# rapidshark_mark_3_5_fuckit.net
KiCad netlist of a schematic drawn in EAGLE
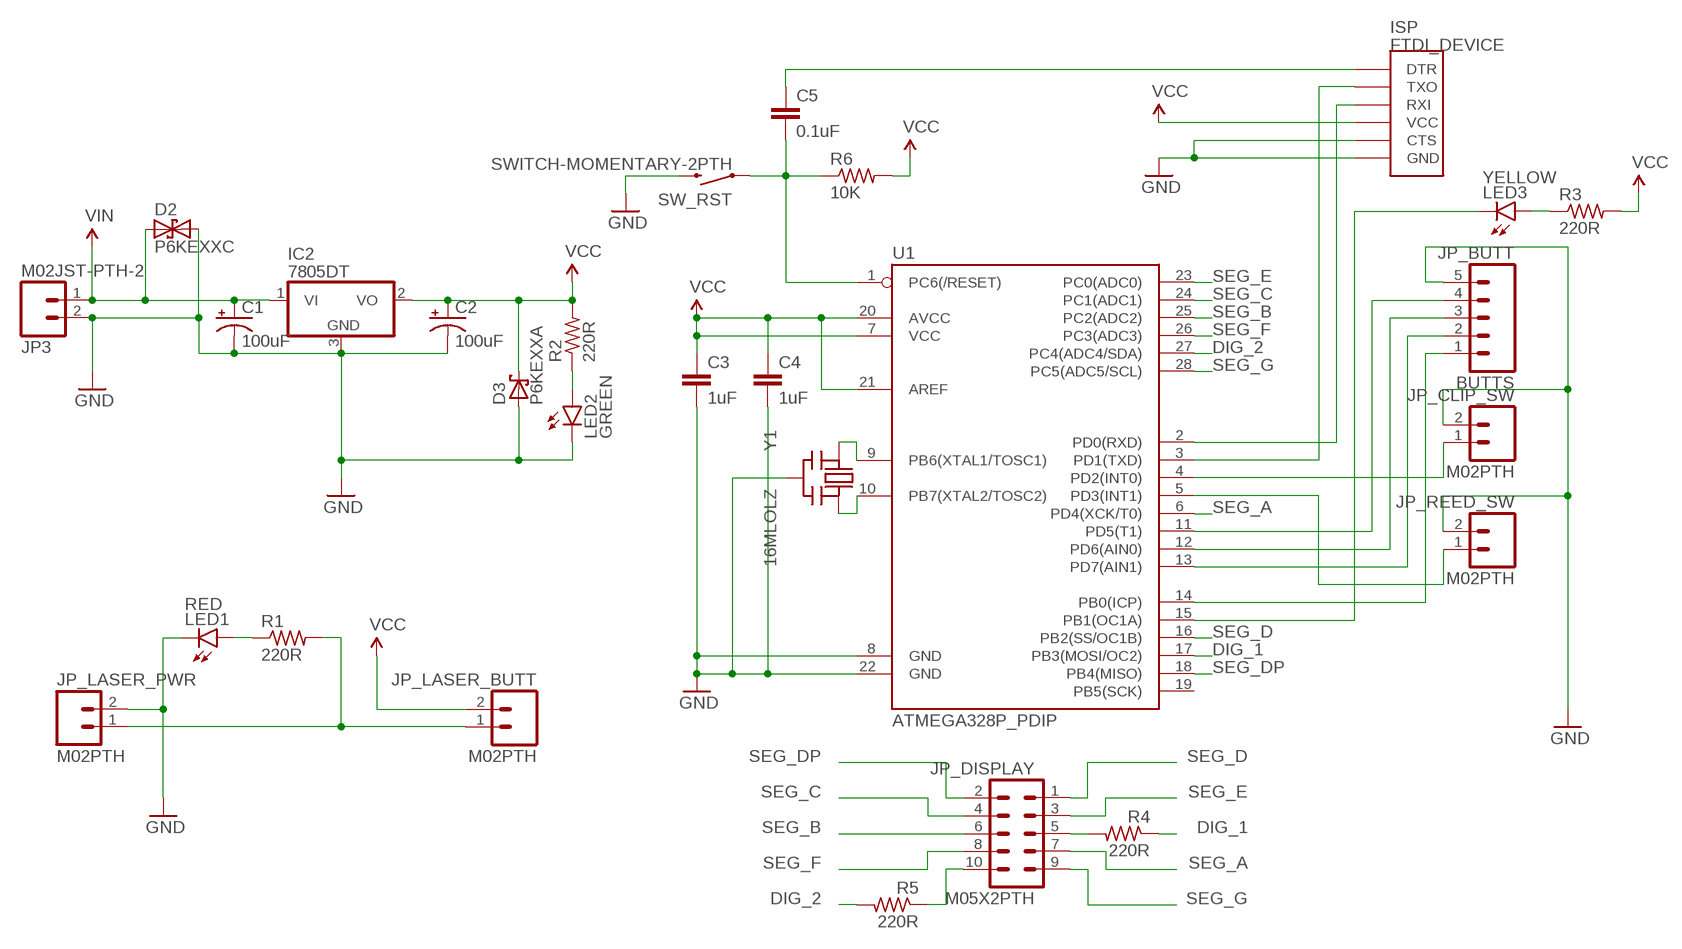
[diagram p0: schematic, sheet 1]

(export (version "E")
  (design (tool "Eeschema 10.0.6"))
  (components
    (comp (ref "C1")
      (value "100uF")
      (footprint "eagle-import:TT2D7L")
      (libsource (lib "eagle-import") (part "CPOL-USTT2D7L"))
    )
    (comp (ref "C2")
      (value "100uF")
      (footprint "eagle-import:TT2D7L")
      (libsource (lib "eagle-import") (part "CPOL-USTT2D7L"))
    )
    (comp (ref "C3")
      (value "1uF")
      (footprint "eagle-import:C025-025X050")
      (libsource (lib "eagle-import") (part "C-EU025-025X050"))
    )
    (comp (ref "C4")
      (value "1uF")
      (footprint "eagle-import:C050-024X044")
      (libsource (lib "eagle-import") (part "C-EU050-024X044"))
    )
    (comp (ref "C5")
      (value "0.1uF")
      (footprint "eagle-import:C025-024X044")
      (libsource (lib "eagle-import") (part "C-EU025-024X044"))
    )
    (comp (ref "D2")
      (value "P6KEXXC")
      (footprint "eagle-import:CB417-15")
      (libsource (lib "eagle-import") (part "P6KEXXC"))
    )
    (comp (ref "D3")
      (value "P6KEXXA")
      (footprint "eagle-import:C1702-15")
      (libsource (lib "eagle-import") (part "P6KEXXA"))
    )
    (comp (ref "IC2")
      (value "7805DT")
      (footprint "eagle-import:TO252")
      (libsource (lib "eagle-import") (part "78DT05"))
    )
    (comp (ref "ISP")
      (value "FTDI_DEVICE")
      (footprint "eagle-import:FTDI_DEVICE_SIDE")
      (libsource (lib "eagle-import") (part "FTDI_DEVICE"))
    )
    (comp (ref "JP3")
      (value "M02JST-PTH-2")
      (footprint "eagle-import:JST-2-PTH")
      (libsource (lib "eagle-import") (part "M02JST-PTH-2"))
    )
    (comp (ref "JP_BUTT")
      (value "BUTTS")
      (footprint "eagle-import:1X05")
      (libsource (lib "eagle-import") (part "M05PTH"))
    )
    (comp (ref "JP_CLIP_SW")
      (value "M02PTH")
      (footprint "eagle-import:1X02")
      (libsource (lib "eagle-import") (part "M02PTH"))
    )
    (comp (ref "JP_DISPLAY")
      (value "M05X2PTH")
      (footprint "eagle-import:AVR_ICSP")
      (libsource (lib "eagle-import") (part "M05X2PTH"))
    )
    (comp (ref "JP_LASER_BUTT")
      (value "M02PTH")
      (footprint "eagle-import:1X02")
      (libsource (lib "eagle-import") (part "M02PTH"))
    )
    (comp (ref "JP_LASER_PWR")
      (value "M02PTH")
      (footprint "eagle-import:1X02")
      (libsource (lib "eagle-import") (part "M02PTH"))
    )
    (comp (ref "JP_REED_SW")
      (value "M02PTH")
      (footprint "eagle-import:1X02")
      (libsource (lib "eagle-import") (part "M02PTH"))
    )
    (comp (ref "LED1")
      (value "RED")
      (footprint "eagle-import:LED3MM")
      (libsource (lib "eagle-import") (part "LED3MM"))
    )
    (comp (ref "LED2")
      (value "GREEN")
      (footprint "eagle-import:LED3MM")
      (libsource (lib "eagle-import") (part "LED3MM"))
    )
    (comp (ref "LED3")
      (value "YELLOW")
      (footprint "eagle-import:LED3MM")
      (libsource (lib "eagle-import") (part "LED3MM"))
    )
    (comp (ref "R1")
      (value "220R")
      (footprint "eagle-import:0204_5")
      (libsource (lib "eagle-import") (part "R-US_0204/5"))
    )
    (comp (ref "R2")
      (value "220R")
      (footprint "eagle-import:0204_5")
      (libsource (lib "eagle-import") (part "R-US_0204/5"))
    )
    (comp (ref "R3")
      (value "220R")
      (footprint "eagle-import:0204_5")
      (libsource (lib "eagle-import") (part "R-US_0204/5"))
    )
    (comp (ref "R4")
      (value "220R")
      (footprint "eagle-import:0204_5")
      (libsource (lib "eagle-import") (part "R-US_0204/5"))
    )
    (comp (ref "R5")
      (value "220R")
      (footprint "eagle-import:0204_5")
      (libsource (lib "eagle-import") (part "R-US_0204/5"))
    )
    (comp (ref "R6")
      (value "10K")
      (footprint "eagle-import:0204_5")
      (libsource (lib "eagle-import") (part "R-US_0204/5"))
    )
    (comp (ref "SW_RST")
      (value "SWITCH-MOMENTARY-2PTH")
      (footprint "eagle-import:TACTILE-PTH")
      (libsource (lib "eagle-import") (part "SWITCH-MOMENTARY-2PTH"))
    )
    (comp (ref "U1")
      (value "ATMEGA328P_PDIP")
      (footprint "eagle-import:DIL28-3")
      (libsource (lib "eagle-import") (part "ATMEGA328P_PDIP"))
    )
    (comp (ref "Y1")
      (value "16MLOLZ")
      (footprint "eagle-import:CERM_OSC")
      (libsource (lib "eagle-import") (part "CERMOSCILL-THM"))
    )
  )
  (nets
    (net (code "1") (name "/DIG_1") (class "Default")
      (node (ref "R4") (pin "1") (pinfunction "1_1") (pintype "passive"))
      (node (ref "U1") (pin "17") (pinfunction "PB3(MOSI/OC2)_17") (pintype "bidirectional"))
    )
    (net (code "2") (name "/DIG_2") (class "Default")
      (node (ref "R5") (pin "2") (pinfunction "2_2") (pintype "passive"))
      (node (ref "U1") (pin "27") (pinfunction "PC4(ADC4/SDA)_27") (pintype "bidirectional"))
    )
    (net (code "3") (name "/SEG_A") (class "Default")
      (node (ref "JP_DISPLAY") (pin "7") (pinfunction "7_7") (pintype "passive"))
      (node (ref "U1") (pin "6") (pinfunction "PD4(XCK/T0)_6") (pintype "bidirectional"))
    )
    (net (code "4") (name "/SEG_B") (class "Default")
      (node (ref "JP_DISPLAY") (pin "6") (pinfunction "6_6") (pintype "passive"))
      (node (ref "U1") (pin "25") (pinfunction "PC2(ADC2)_25") (pintype "bidirectional"))
    )
    (net (code "5") (name "/SEG_C") (class "Default")
      (node (ref "JP_DISPLAY") (pin "4") (pinfunction "4_4") (pintype "passive"))
      (node (ref "U1") (pin "24") (pinfunction "PC1(ADC1)_24") (pintype "bidirectional"))
    )
    (net (code "6") (name "/SEG_D") (class "Default")
      (node (ref "JP_DISPLAY") (pin "1") (pinfunction "1_1") (pintype "passive"))
      (node (ref "U1") (pin "16") (pinfunction "PB2(SS/OC1B)_16") (pintype "bidirectional"))
    )
    (net (code "7") (name "/SEG_DP") (class "Default")
      (node (ref "JP_DISPLAY") (pin "2") (pinfunction "2_2") (pintype "passive"))
      (node (ref "U1") (pin "18") (pinfunction "PB4(MISO)_18") (pintype "bidirectional"))
    )
    (net (code "8") (name "/SEG_E") (class "Default")
      (node (ref "JP_DISPLAY") (pin "3") (pinfunction "3_3") (pintype "passive"))
      (node (ref "U1") (pin "23") (pinfunction "PC0(ADC0)_23") (pintype "bidirectional"))
    )
    (net (code "9") (name "/SEG_F") (class "Default")
      (node (ref "JP_DISPLAY") (pin "8") (pinfunction "8_8") (pintype "passive"))
      (node (ref "U1") (pin "26") (pinfunction "PC3(ADC3)_26") (pintype "bidirectional"))
    )
    (net (code "10") (name "/SEG_G") (class "Default")
      (node (ref "JP_DISPLAY") (pin "9") (pinfunction "9_9") (pintype "passive"))
      (node (ref "U1") (pin "28") (pinfunction "PC5(ADC5/SCL)_28") (pintype "bidirectional"))
    )
    (net (code "11") (name "GND") (class "Default")
      (node (ref "C1") (pin "-") (pinfunction "-_-") (pintype "passive"))
      (node (ref "C2") (pin "-") (pinfunction "-_-") (pintype "passive"))
      (node (ref "C3") (pin "2") (pinfunction "2_2") (pintype "passive"))
      (node (ref "C4") (pin "2") (pinfunction "2_2") (pintype "passive"))
      (node (ref "D2") (pin "C") (pinfunction "2_C") (pintype "passive"))
      (node (ref "D3") (pin "A") (pinfunction "A_A") (pintype "passive"))
      (node (ref "IC2") (pin "3") (pinfunction "GND_3") (pintype "passive"))
      (node (ref "ISP") (pin "P$5") (pinfunction "CTS_P$5") (pintype "bidirectional"))
      (node (ref "ISP") (pin "P$6") (pinfunction "GND_P$6") (pintype "bidirectional"))
      (node (ref "JP3") (pin "2") (pinfunction "2_2") (pintype "passive"))
      (node (ref "JP_BUTT") (pin "5") (pinfunction "5_5") (pintype "passive"))
      (node (ref "JP_CLIP_SW") (pin "2") (pinfunction "2_2") (pintype "passive"))
      (node (ref "JP_LASER_PWR") (pin "2") (pinfunction "2_2") (pintype "passive"))
      (node (ref "JP_REED_SW") (pin "2") (pinfunction "2_2") (pintype "passive"))
      (node (ref "LED1") (pin "K") (pinfunction "C_K") (pintype "passive"))
      (node (ref "LED2") (pin "K") (pinfunction "C_K") (pintype "passive"))
      (node (ref "SW_RST") (pin "3") (pinfunction "2_3") (pintype "passive"))
      (node (ref "U1") (pin "22") (pinfunction "GND_22") (pintype "bidirectional"))
      (node (ref "U1") (pin "8") (pinfunction "GND_8") (pintype "bidirectional"))
      (node (ref "Y1") (pin "P$2") (pinfunction "GND_P$2") (pintype "bidirectional"))
    )
    (net (code "12") (name "Net-(ISP-DTR)") (class "Default")
      (node (ref "C5") (pin "1") (pinfunction "1_1") (pintype "passive"))
      (node (ref "ISP") (pin "P$1") (pinfunction "DTR_P$1") (pintype "bidirectional"))
    )
    (net (code "13") (name "Net-(ISP-RXI)") (class "Default")
      (node (ref "ISP") (pin "P$3") (pinfunction "RXI_P$3") (pintype "bidirectional"))
      (node (ref "U1") (pin "2") (pinfunction "PD0(RXD)_2") (pintype "bidirectional"))
    )
    (net (code "14") (name "Net-(ISP-TXO)") (class "Default")
      (node (ref "ISP") (pin "P$2") (pinfunction "TXO_P$2") (pintype "bidirectional"))
      (node (ref "U1") (pin "3") (pinfunction "PD1(TXD)_3") (pintype "bidirectional"))
    )
    (net (code "15") (name "Net-(JP_DISPLAY-Pad5)") (class "Default")
      (node (ref "JP_DISPLAY") (pin "5") (pinfunction "5_5") (pintype "passive"))
      (node (ref "R4") (pin "2") (pinfunction "2_2") (pintype "passive"))
    )
    (net (code "16") (name "Net-(JP_DISPLAY-Pad10)") (class "Default")
      (node (ref "JP_DISPLAY") (pin "10") (pinfunction "10_10") (pintype "passive"))
      (node (ref "R5") (pin "1") (pinfunction "1_1") (pintype "passive"))
    )
    (net (code "17") (name "Net-(JP_LASER_BUTT-Pad1)") (class "Default")
      (node (ref "JP_LASER_BUTT") (pin "1") (pinfunction "1_1") (pintype "passive"))
      (node (ref "JP_LASER_PWR") (pin "1") (pinfunction "1_1") (pintype "passive"))
      (node (ref "R1") (pin "2") (pinfunction "2_2") (pintype "passive"))
    )
    (net (code "18") (name "Net-(LED1-PadA)") (class "Default")
      (node (ref "LED1") (pin "A") (pinfunction "A_A") (pintype "passive"))
      (node (ref "R1") (pin "1") (pinfunction "1_1") (pintype "passive"))
    )
    (net (code "19") (name "Net-(LED2-PadA)") (class "Default")
      (node (ref "LED2") (pin "A") (pinfunction "A_A") (pintype "passive"))
      (node (ref "R2") (pin "1") (pinfunction "1_1") (pintype "passive"))
    )
    (net (code "20") (name "Net-(LED3-C)") (class "Default")
      (node (ref "LED3") (pin "K") (pinfunction "C_K") (pintype "passive"))
      (node (ref "U1") (pin "15") (pinfunction "PB1(OC1A)_15") (pintype "bidirectional"))
    )
    (net (code "21") (name "Net-(LED3-PadA)") (class "Default")
      (node (ref "LED3") (pin "A") (pinfunction "A_A") (pintype "passive"))
      (node (ref "R3") (pin "1") (pinfunction "1_1") (pintype "passive"))
    )
    (net (code "22") (name "Net-(U1-PB0(ICP))") (class "Default")
      (node (ref "JP_BUTT") (pin "1") (pinfunction "1_1") (pintype "passive"))
      (node (ref "U1") (pin "14") (pinfunction "PB0(ICP)_14") (pintype "bidirectional"))
    )
    (net (code "23") (name "Net-(U1-PB6(XTAL1{slash}TOSC1))") (class "Default")
      (node (ref "U1") (pin "9") (pinfunction "PB6(XTAL1/TOSC1)_9") (pintype "bidirectional"))
      (node (ref "Y1") (pin "P$1") (pinfunction "IN_P$1") (pintype "bidirectional"))
    )
    (net (code "24") (name "Net-(U1-PB7(XTAL2{slash}TOSC2))") (class "Default")
      (node (ref "U1") (pin "10") (pinfunction "PB7(XTAL2/TOSC2)_10") (pintype "bidirectional"))
      (node (ref "Y1") (pin "P$3") (pinfunction "OUT_P$3") (pintype "bidirectional"))
    )
    (net (code "25") (name "Net-(U1-PC6({slash}RESET))") (class "Default")
      (node (ref "C5") (pin "2") (pinfunction "2_2") (pintype "passive"))
      (node (ref "R6") (pin "1") (pinfunction "1_1") (pintype "passive"))
      (node (ref "SW_RST") (pin "1") (pinfunction "1_1") (pintype "passive"))
      (node (ref "U1") (pin "1") (pinfunction "PC6(/RESET)_1") (pintype "bidirectional"))
    )
    (net (code "26") (name "Net-(U1-PD2(INT0))") (class "Default")
      (node (ref "JP_CLIP_SW") (pin "1") (pinfunction "1_1") (pintype "passive"))
      (node (ref "U1") (pin "4") (pinfunction "PD2(INT0)_4") (pintype "bidirectional"))
    )
    (net (code "27") (name "Net-(U1-PD3(INT1))") (class "Default")
      (node (ref "JP_REED_SW") (pin "1") (pinfunction "1_1") (pintype "passive"))
      (node (ref "U1") (pin "5") (pinfunction "PD3(INT1)_5") (pintype "bidirectional"))
    )
    (net (code "28") (name "Net-(U1-PD5(T1))") (class "Default")
      (node (ref "JP_BUTT") (pin "4") (pinfunction "4_4") (pintype "passive"))
      (node (ref "U1") (pin "11") (pinfunction "PD5(T1)_11") (pintype "bidirectional"))
    )
    (net (code "29") (name "Net-(U1-PD6(AIN0))") (class "Default")
      (node (ref "JP_BUTT") (pin "3") (pinfunction "3_3") (pintype "passive"))
      (node (ref "U1") (pin "12") (pinfunction "PD6(AIN0)_12") (pintype "bidirectional"))
    )
    (net (code "30") (name "Net-(U1-PD7(AIN1))") (class "Default")
      (node (ref "JP_BUTT") (pin "2") (pinfunction "2_2") (pintype "passive"))
      (node (ref "U1") (pin "13") (pinfunction "PD7(AIN1)_13") (pintype "bidirectional"))
    )
    (net (code "31") (name "VCC") (class "Default")
      (node (ref "C2") (pin "+") (pinfunction "+_+") (pintype "passive"))
      (node (ref "C3") (pin "1") (pinfunction "1_1") (pintype "passive"))
      (node (ref "C4") (pin "1") (pinfunction "1_1") (pintype "passive"))
      (node (ref "D3") (pin "C") (pinfunction "C_C") (pintype "passive"))
      (node (ref "IC2") (pin "2") (pinfunction "VO_2") (pintype "passive"))
      (node (ref "ISP") (pin "P$4") (pinfunction "VCC_P$4") (pintype "bidirectional"))
      (node (ref "JP_LASER_BUTT") (pin "2") (pinfunction "2_2") (pintype "passive"))
      (node (ref "R2") (pin "2") (pinfunction "2_2") (pintype "passive"))
      (node (ref "R3") (pin "2") (pinfunction "2_2") (pintype "passive"))
      (node (ref "R6") (pin "2") (pinfunction "2_2") (pintype "passive"))
      (node (ref "U1") (pin "20") (pinfunction "AVCC_20") (pintype "bidirectional"))
      (node (ref "U1") (pin "21") (pinfunction "AREF_21") (pintype "bidirectional"))
      (node (ref "U1") (pin "7") (pinfunction "VCC_7") (pintype "bidirectional"))
    )
    (net (code "32") (name "VIN") (class "Default")
      (node (ref "C1") (pin "+") (pinfunction "+_+") (pintype "passive"))
      (node (ref "D2") (pin "A") (pinfunction "1_A") (pintype "passive"))
      (node (ref "IC2") (pin "1") (pinfunction "VI_1") (pintype "input"))
      (node (ref "JP3") (pin "1") (pinfunction "1_1") (pintype "passive"))
    )
    (net (code "33") (name "unconnected-(U1-PB5(SCK)-Pad19)") (class "Default")
      (node (ref "U1") (pin "19") (pinfunction "PB5(SCK)_19") (pintype "bidirectional"))
    )
  )
)
